# TB_Driver.net
KiCad netlist of a schematic drawn in Altium Designer
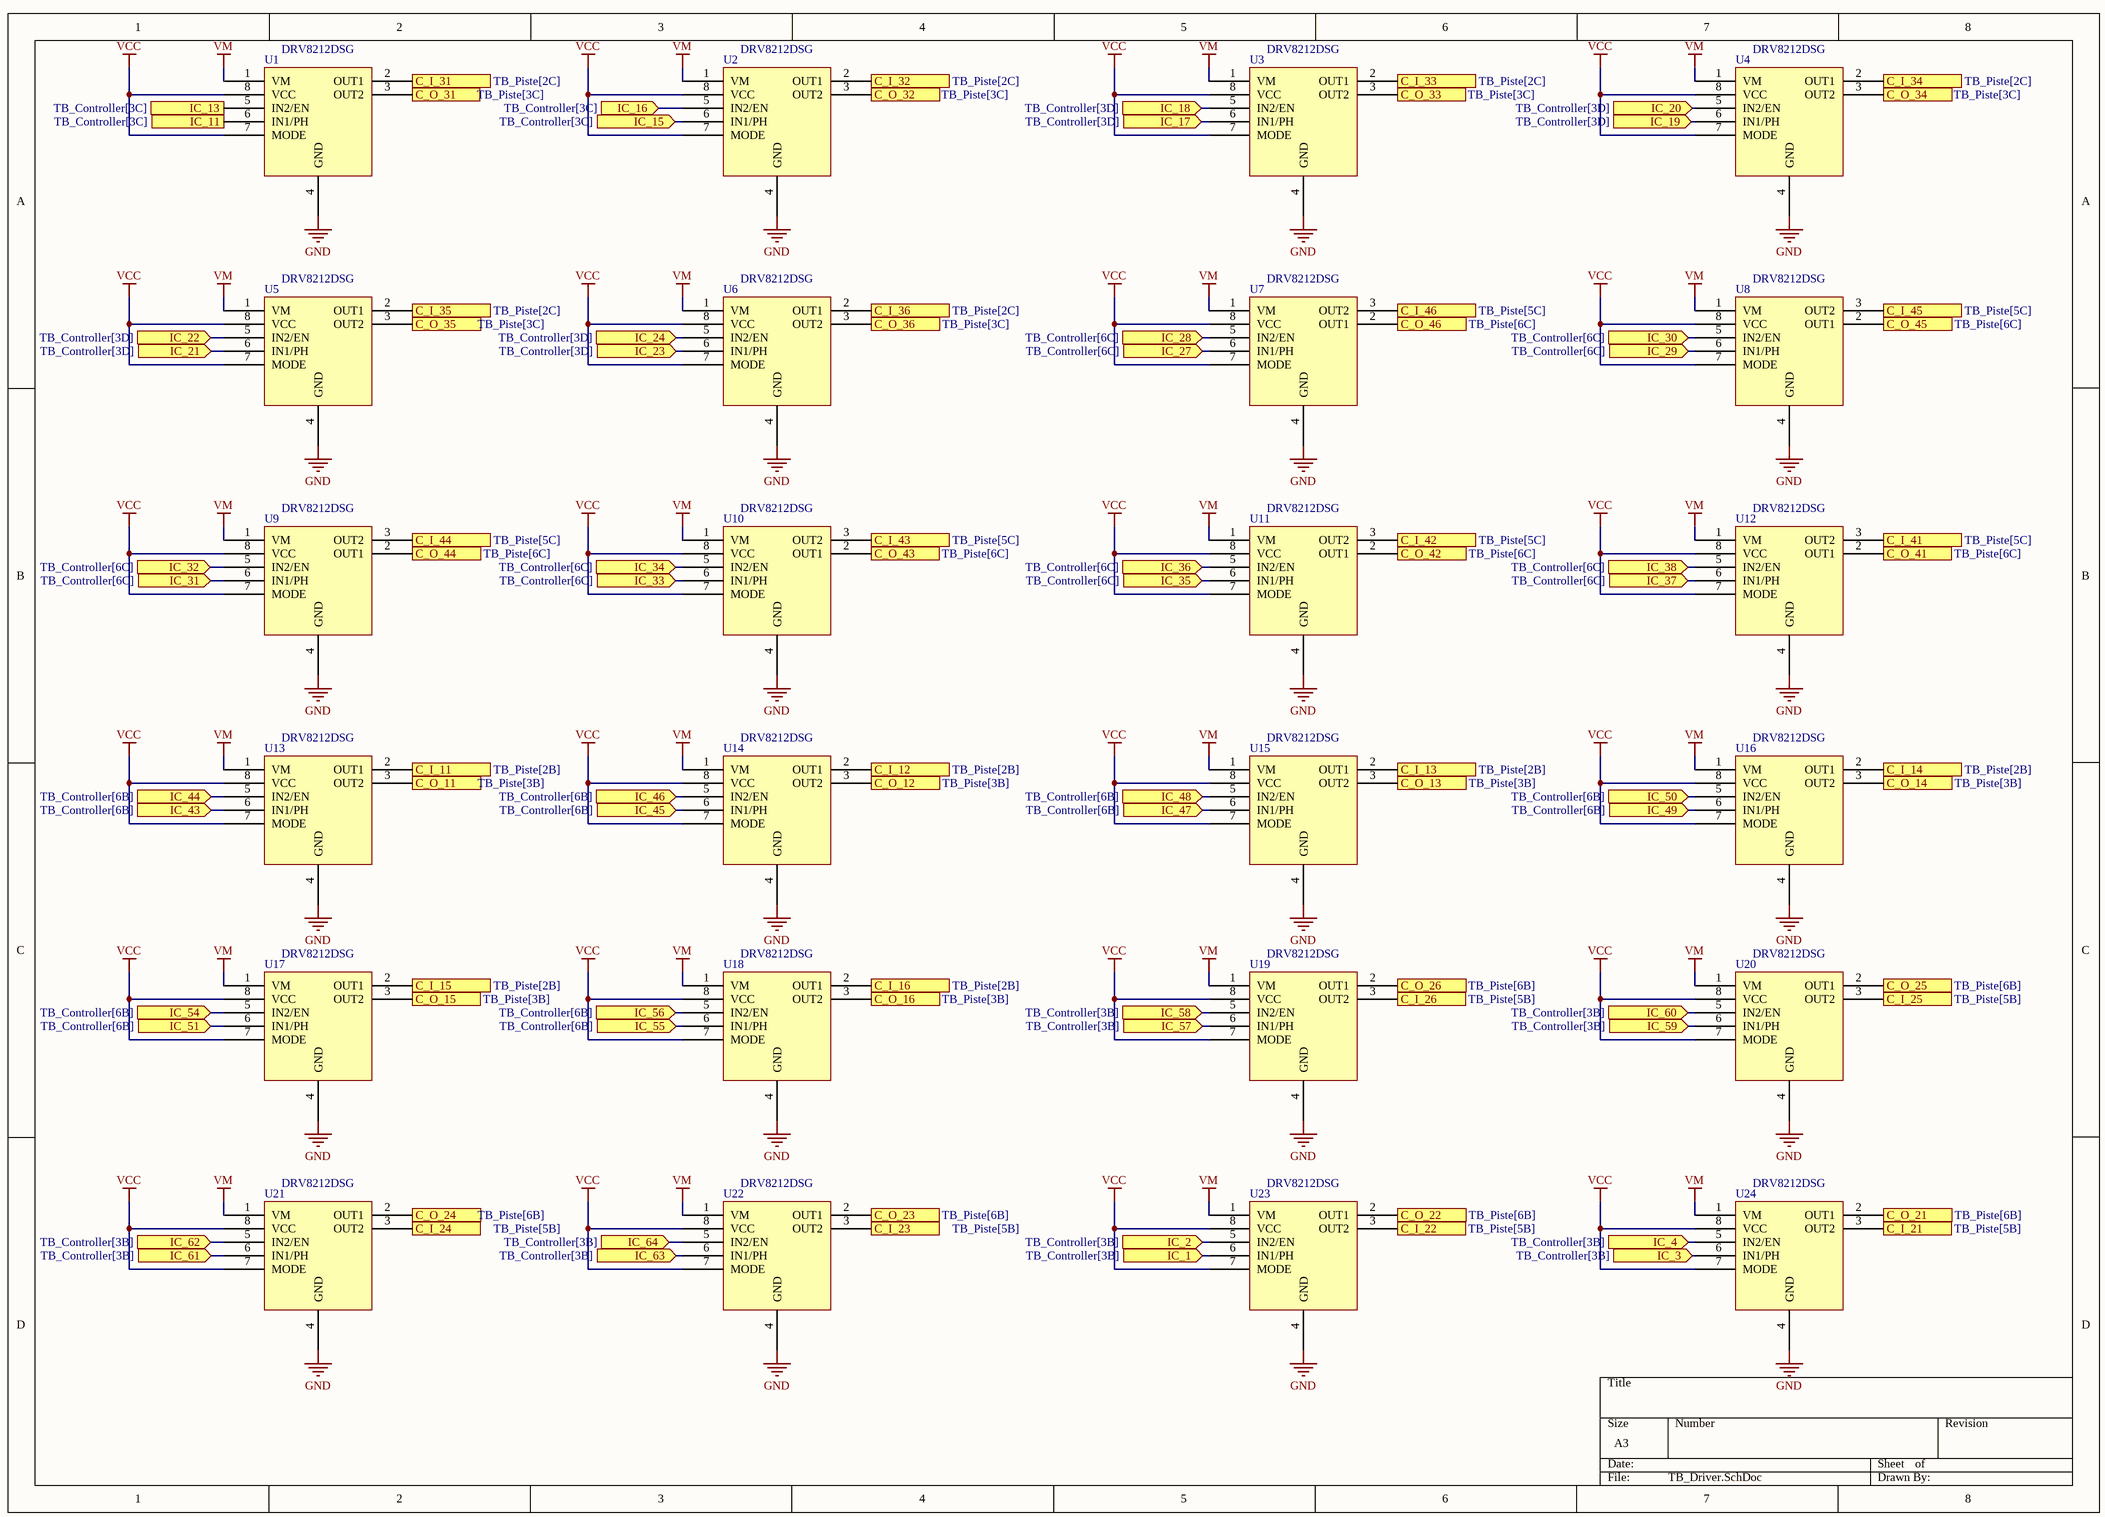
[diagram p0: TB_Driver.SchDoc]

(export (version "E")
  (design (tool "Eeschema 10.0.6"))
  (components
    (comp (ref "U1")
      (value "DRV8212DSG")
      (footprint "DRV8212DSGR")
      (libsource (lib "TB_Components") (part "DRV8212DSG"))
    )
    (comp (ref "U2")
      (value "DRV8212DSG")
      (footprint "DRV8212DSGR")
      (libsource (lib "TB_Components") (part "DRV8212DSG"))
    )
    (comp (ref "U3")
      (value "DRV8212DSG")
      (footprint "DRV8212DSGR")
      (libsource (lib "TB_Components") (part "DRV8212DSG"))
    )
    (comp (ref "U4")
      (value "DRV8212DSG")
      (footprint "DRV8212DSGR")
      (libsource (lib "TB_Components") (part "DRV8212DSG"))
    )
    (comp (ref "U5")
      (value "DRV8212DSG")
      (footprint "DRV8212DSGR")
      (libsource (lib "TB_Components") (part "DRV8212DSG"))
    )
    (comp (ref "U6")
      (value "DRV8212DSG")
      (footprint "DRV8212DSGR")
      (libsource (lib "TB_Components") (part "DRV8212DSG"))
    )
    (comp (ref "U7")
      (value "DRV8212DSG")
      (footprint "DRV8212DSGR")
      (libsource (lib "") (part "DRV8212DSG_1"))
    )
    (comp (ref "U8")
      (value "DRV8212DSG")
      (footprint "DRV8212DSGR")
      (libsource (lib "") (part "DRV8212DSG_1"))
    )
    (comp (ref "U9")
      (value "DRV8212DSG")
      (footprint "DRV8212DSGR")
      (libsource (lib "") (part "DRV8212DSG_1"))
    )
    (comp (ref "U10")
      (value "DRV8212DSG")
      (footprint "DRV8212DSGR")
      (libsource (lib "") (part "DRV8212DSG_1"))
    )
    (comp (ref "U11")
      (value "DRV8212DSG")
      (footprint "DRV8212DSGR")
      (libsource (lib "") (part "DRV8212DSG_1"))
    )
    (comp (ref "U12")
      (value "DRV8212DSG")
      (footprint "DRV8212DSGR")
      (libsource (lib "") (part "DRV8212DSG_1"))
    )
    (comp (ref "U13")
      (value "DRV8212DSG")
      (footprint "DRV8212DSGR")
      (libsource (lib "TB_Components") (part "DRV8212DSG"))
    )
    (comp (ref "U14")
      (value "DRV8212DSG")
      (footprint "DRV8212DSGR")
      (libsource (lib "TB_Components") (part "DRV8212DSG"))
    )
    (comp (ref "U15")
      (value "DRV8212DSG")
      (footprint "DRV8212DSGR")
      (libsource (lib "TB_Components") (part "DRV8212DSG"))
    )
    (comp (ref "U16")
      (value "DRV8212DSG")
      (footprint "DRV8212DSGR")
      (libsource (lib "TB_Components") (part "DRV8212DSG"))
    )
    (comp (ref "U17")
      (value "DRV8212DSG")
      (footprint "DRV8212DSGR")
      (libsource (lib "TB_Components") (part "DRV8212DSG"))
    )
    (comp (ref "U18")
      (value "DRV8212DSG")
      (footprint "DRV8212DSGR")
      (libsource (lib "TB_Components") (part "DRV8212DSG"))
    )
    (comp (ref "U19")
      (value "DRV8212DSG")
      (footprint "DRV8212DSGR")
      (libsource (lib "TB_Components") (part "DRV8212DSG"))
    )
    (comp (ref "U20")
      (value "DRV8212DSG")
      (footprint "DRV8212DSGR")
      (libsource (lib "TB_Components") (part "DRV8212DSG"))
    )
    (comp (ref "U21")
      (value "DRV8212DSG")
      (footprint "DRV8212DSGR")
      (libsource (lib "TB_Components") (part "DRV8212DSG"))
    )
    (comp (ref "U22")
      (value "DRV8212DSG")
      (footprint "DRV8212DSGR")
      (libsource (lib "TB_Components") (part "DRV8212DSG"))
    )
    (comp (ref "U23")
      (value "DRV8212DSG")
      (footprint "DRV8212DSGR")
      (libsource (lib "TB_Components") (part "DRV8212DSG"))
    )
    (comp (ref "U24")
      (value "DRV8212DSG")
      (footprint "DRV8212DSGR")
      (libsource (lib "TB_Components") (part "DRV8212DSG"))
    )
  )
  (nets
    (net (code "1") (name "/C_I_11") (class "Default")
      (node (ref "U13") (pin "2") (pinfunction "OUT1_2") (pintype "passive"))
    )
    (net (code "2") (name "/C_I_12") (class "Default")
      (node (ref "U14") (pin "2") (pinfunction "OUT1_2") (pintype "passive"))
    )
    (net (code "3") (name "/C_I_13") (class "Default")
      (node (ref "U15") (pin "2") (pinfunction "OUT1_2") (pintype "passive"))
    )
    (net (code "4") (name "/C_I_14") (class "Default")
      (node (ref "U16") (pin "2") (pinfunction "OUT1_2") (pintype "passive"))
    )
    (net (code "5") (name "/C_I_15") (class "Default")
      (node (ref "U17") (pin "2") (pinfunction "OUT1_2") (pintype "passive"))
    )
    (net (code "6") (name "/C_I_16") (class "Default")
      (node (ref "U18") (pin "2") (pinfunction "OUT1_2") (pintype "passive"))
    )
    (net (code "7") (name "/C_I_21") (class "Default")
      (node (ref "U24") (pin "3") (pinfunction "OUT2_3") (pintype "passive"))
    )
    (net (code "8") (name "/C_I_22") (class "Default")
      (node (ref "U23") (pin "3") (pinfunction "OUT2_3") (pintype "passive"))
    )
    (net (code "9") (name "/C_I_23") (class "Default")
      (node (ref "U22") (pin "3") (pinfunction "OUT2_3") (pintype "passive"))
    )
    (net (code "10") (name "/C_I_24") (class "Default")
      (node (ref "U21") (pin "3") (pinfunction "OUT2_3") (pintype "passive"))
    )
    (net (code "11") (name "/C_I_25") (class "Default")
      (node (ref "U20") (pin "3") (pinfunction "OUT2_3") (pintype "passive"))
    )
    (net (code "12") (name "/C_I_26") (class "Default")
      (node (ref "U19") (pin "3") (pinfunction "OUT2_3") (pintype "passive"))
    )
    (net (code "13") (name "/C_I_31") (class "Default")
      (node (ref "U1") (pin "2") (pinfunction "OUT1_2") (pintype "passive"))
    )
    (net (code "14") (name "/C_I_32") (class "Default")
      (node (ref "U2") (pin "2") (pinfunction "OUT1_2") (pintype "passive"))
    )
    (net (code "15") (name "/C_I_33") (class "Default")
      (node (ref "U3") (pin "2") (pinfunction "OUT1_2") (pintype "passive"))
    )
    (net (code "16") (name "/C_I_34") (class "Default")
      (node (ref "U4") (pin "2") (pinfunction "OUT1_2") (pintype "passive"))
    )
    (net (code "17") (name "/C_I_35") (class "Default")
      (node (ref "U5") (pin "2") (pinfunction "OUT1_2") (pintype "passive"))
    )
    (net (code "18") (name "/C_I_36") (class "Default")
      (node (ref "U6") (pin "2") (pinfunction "OUT1_2") (pintype "passive"))
    )
    (net (code "19") (name "/C_I_41") (class "Default")
      (node (ref "U12") (pin "3") (pinfunction "OUT2_3") (pintype "passive"))
    )
    (net (code "20") (name "/C_I_42") (class "Default")
      (node (ref "U11") (pin "3") (pinfunction "OUT2_3") (pintype "passive"))
    )
    (net (code "21") (name "/C_I_43") (class "Default")
      (node (ref "U10") (pin "3") (pinfunction "OUT2_3") (pintype "passive"))
    )
    (net (code "22") (name "/C_I_44") (class "Default")
      (node (ref "U9") (pin "3") (pinfunction "OUT2_3") (pintype "passive"))
    )
    (net (code "23") (name "/C_I_45") (class "Default")
      (node (ref "U8") (pin "3") (pinfunction "OUT2_3") (pintype "passive"))
    )
    (net (code "24") (name "/C_I_46") (class "Default")
      (node (ref "U7") (pin "3") (pinfunction "OUT2_3") (pintype "passive"))
    )
    (net (code "25") (name "/C_O_11") (class "Default")
      (node (ref "U13") (pin "3") (pinfunction "OUT2_3") (pintype "passive"))
    )
    (net (code "26") (name "/C_O_12") (class "Default")
      (node (ref "U14") (pin "3") (pinfunction "OUT2_3") (pintype "passive"))
    )
    (net (code "27") (name "/C_O_13") (class "Default")
      (node (ref "U15") (pin "3") (pinfunction "OUT2_3") (pintype "passive"))
    )
    (net (code "28") (name "/C_O_14") (class "Default")
      (node (ref "U16") (pin "3") (pinfunction "OUT2_3") (pintype "passive"))
    )
    (net (code "29") (name "/C_O_15") (class "Default")
      (node (ref "U17") (pin "3") (pinfunction "OUT2_3") (pintype "passive"))
    )
    (net (code "30") (name "/C_O_16") (class "Default")
      (node (ref "U18") (pin "3") (pinfunction "OUT2_3") (pintype "passive"))
    )
    (net (code "31") (name "/C_O_21") (class "Default")
      (node (ref "U24") (pin "2") (pinfunction "OUT1_2") (pintype "passive"))
    )
    (net (code "32") (name "/C_O_22") (class "Default")
      (node (ref "U23") (pin "2") (pinfunction "OUT1_2") (pintype "passive"))
    )
    (net (code "33") (name "/C_O_23") (class "Default")
      (node (ref "U22") (pin "2") (pinfunction "OUT1_2") (pintype "passive"))
    )
    (net (code "34") (name "/C_O_24") (class "Default")
      (node (ref "U21") (pin "2") (pinfunction "OUT1_2") (pintype "passive"))
    )
    (net (code "35") (name "/C_O_25") (class "Default")
      (node (ref "U20") (pin "2") (pinfunction "OUT1_2") (pintype "passive"))
    )
    (net (code "36") (name "/C_O_26") (class "Default")
      (node (ref "U19") (pin "2") (pinfunction "OUT1_2") (pintype "passive"))
    )
    (net (code "37") (name "/C_O_31") (class "Default")
      (node (ref "U1") (pin "3") (pinfunction "OUT2_3") (pintype "passive"))
    )
    (net (code "38") (name "/C_O_32") (class "Default")
      (node (ref "U2") (pin "3") (pinfunction "OUT2_3") (pintype "passive"))
    )
    (net (code "39") (name "/C_O_33") (class "Default")
      (node (ref "U3") (pin "3") (pinfunction "OUT2_3") (pintype "passive"))
    )
    (net (code "40") (name "/C_O_34") (class "Default")
      (node (ref "U4") (pin "3") (pinfunction "OUT2_3") (pintype "passive"))
    )
    (net (code "41") (name "/C_O_35") (class "Default")
      (node (ref "U5") (pin "3") (pinfunction "OUT2_3") (pintype "passive"))
    )
    (net (code "42") (name "/C_O_36") (class "Default")
      (node (ref "U6") (pin "3") (pinfunction "OUT2_3") (pintype "passive"))
    )
    (net (code "43") (name "/C_O_41") (class "Default")
      (node (ref "U12") (pin "2") (pinfunction "OUT1_2") (pintype "passive"))
    )
    (net (code "44") (name "/C_O_42") (class "Default")
      (node (ref "U11") (pin "2") (pinfunction "OUT1_2") (pintype "passive"))
    )
    (net (code "45") (name "/C_O_43") (class "Default")
      (node (ref "U10") (pin "2") (pinfunction "OUT1_2") (pintype "passive"))
    )
    (net (code "46") (name "/C_O_44") (class "Default")
      (node (ref "U9") (pin "2") (pinfunction "OUT1_2") (pintype "passive"))
    )
    (net (code "47") (name "/C_O_45") (class "Default")
      (node (ref "U8") (pin "2") (pinfunction "OUT1_2") (pintype "passive"))
    )
    (net (code "48") (name "/C_O_46") (class "Default")
      (node (ref "U7") (pin "2") (pinfunction "OUT1_2") (pintype "passive"))
    )
    (net (code "49") (name "/IC_1") (class "Default")
      (node (ref "U23") (pin "6") (pinfunction "IN1/PH_6") (pintype "passive"))
    )
    (net (code "50") (name "/IC_2") (class "Default")
      (node (ref "U23") (pin "5") (pinfunction "IN2/EN_5") (pintype "passive"))
    )
    (net (code "51") (name "/IC_3") (class "Default")
      (node (ref "U24") (pin "6") (pinfunction "IN1/PH_6") (pintype "passive"))
    )
    (net (code "52") (name "/IC_4") (class "Default")
      (node (ref "U24") (pin "5") (pinfunction "IN2/EN_5") (pintype "passive"))
    )
    (net (code "53") (name "/IC_11") (class "Default")
      (node (ref "U1") (pin "6") (pinfunction "IN1/PH_6") (pintype "passive"))
    )
    (net (code "54") (name "/IC_13") (class "Default")
      (node (ref "U1") (pin "5") (pinfunction "IN2/EN_5") (pintype "passive"))
    )
    (net (code "55") (name "/IC_15") (class "Default")
      (node (ref "U2") (pin "6") (pinfunction "IN1/PH_6") (pintype "passive"))
    )
    (net (code "56") (name "/IC_16") (class "Default")
      (node (ref "U2") (pin "5") (pinfunction "IN2/EN_5") (pintype "passive"))
    )
    (net (code "57") (name "/IC_17") (class "Default")
      (node (ref "U3") (pin "6") (pinfunction "IN1/PH_6") (pintype "passive"))
    )
    (net (code "58") (name "/IC_18") (class "Default")
      (node (ref "U3") (pin "5") (pinfunction "IN2/EN_5") (pintype "passive"))
    )
    (net (code "59") (name "/IC_19") (class "Default")
      (node (ref "U4") (pin "6") (pinfunction "IN1/PH_6") (pintype "passive"))
    )
    (net (code "60") (name "/IC_20") (class "Default")
      (node (ref "U4") (pin "5") (pinfunction "IN2/EN_5") (pintype "passive"))
    )
    (net (code "61") (name "/IC_21") (class "Default")
      (node (ref "U5") (pin "6") (pinfunction "IN1/PH_6") (pintype "passive"))
    )
    (net (code "62") (name "/IC_22") (class "Default")
      (node (ref "U5") (pin "5") (pinfunction "IN2/EN_5") (pintype "passive"))
    )
    (net (code "63") (name "/IC_23") (class "Default")
      (node (ref "U6") (pin "6") (pinfunction "IN1/PH_6") (pintype "passive"))
    )
    (net (code "64") (name "/IC_24") (class "Default")
      (node (ref "U6") (pin "5") (pinfunction "IN2/EN_5") (pintype "passive"))
    )
    (net (code "65") (name "/IC_27") (class "Default")
      (node (ref "U7") (pin "6") (pinfunction "IN1/PH_6") (pintype "passive"))
    )
    (net (code "66") (name "/IC_28") (class "Default")
      (node (ref "U7") (pin "5") (pinfunction "IN2/EN_5") (pintype "passive"))
    )
    (net (code "67") (name "/IC_29") (class "Default")
      (node (ref "U8") (pin "6") (pinfunction "IN1/PH_6") (pintype "passive"))
    )
    (net (code "68") (name "/IC_30") (class "Default")
      (node (ref "U8") (pin "5") (pinfunction "IN2/EN_5") (pintype "passive"))
    )
    (net (code "69") (name "/IC_31") (class "Default")
      (node (ref "U9") (pin "6") (pinfunction "IN1/PH_6") (pintype "passive"))
    )
    (net (code "70") (name "/IC_32") (class "Default")
      (node (ref "U9") (pin "5") (pinfunction "IN2/EN_5") (pintype "passive"))
    )
    (net (code "71") (name "/IC_33") (class "Default")
      (node (ref "U10") (pin "6") (pinfunction "IN1/PH_6") (pintype "passive"))
    )
    (net (code "72") (name "/IC_34") (class "Default")
      (node (ref "U10") (pin "5") (pinfunction "IN2/EN_5") (pintype "passive"))
    )
    (net (code "73") (name "/IC_35") (class "Default")
      (node (ref "U11") (pin "6") (pinfunction "IN1/PH_6") (pintype "passive"))
    )
    (net (code "74") (name "/IC_36") (class "Default")
      (node (ref "U11") (pin "5") (pinfunction "IN2/EN_5") (pintype "passive"))
    )
    (net (code "75") (name "/IC_37") (class "Default")
      (node (ref "U12") (pin "6") (pinfunction "IN1/PH_6") (pintype "passive"))
    )
    (net (code "76") (name "/IC_38") (class "Default")
      (node (ref "U12") (pin "5") (pinfunction "IN2/EN_5") (pintype "passive"))
    )
    (net (code "77") (name "/IC_43") (class "Default")
      (node (ref "U13") (pin "6") (pinfunction "IN1/PH_6") (pintype "passive"))
    )
    (net (code "78") (name "/IC_44") (class "Default")
      (node (ref "U13") (pin "5") (pinfunction "IN2/EN_5") (pintype "passive"))
    )
    (net (code "79") (name "/IC_45") (class "Default")
      (node (ref "U14") (pin "6") (pinfunction "IN1/PH_6") (pintype "passive"))
    )
    (net (code "80") (name "/IC_46") (class "Default")
      (node (ref "U14") (pin "5") (pinfunction "IN2/EN_5") (pintype "passive"))
    )
    (net (code "81") (name "/IC_47") (class "Default")
      (node (ref "U15") (pin "6") (pinfunction "IN1/PH_6") (pintype "passive"))
    )
    (net (code "82") (name "/IC_48") (class "Default")
      (node (ref "U15") (pin "5") (pinfunction "IN2/EN_5") (pintype "passive"))
    )
    (net (code "83") (name "/IC_49") (class "Default")
      (node (ref "U16") (pin "6") (pinfunction "IN1/PH_6") (pintype "passive"))
    )
    (net (code "84") (name "/IC_50") (class "Default")
      (node (ref "U16") (pin "5") (pinfunction "IN2/EN_5") (pintype "passive"))
    )
    (net (code "85") (name "/IC_51") (class "Default")
      (node (ref "U17") (pin "6") (pinfunction "IN1/PH_6") (pintype "passive"))
    )
    (net (code "86") (name "/IC_54") (class "Default")
      (node (ref "U17") (pin "5") (pinfunction "IN2/EN_5") (pintype "passive"))
    )
    (net (code "87") (name "/IC_55") (class "Default")
      (node (ref "U18") (pin "6") (pinfunction "IN1/PH_6") (pintype "passive"))
    )
    (net (code "88") (name "/IC_56") (class "Default")
      (node (ref "U18") (pin "5") (pinfunction "IN2/EN_5") (pintype "passive"))
    )
    (net (code "89") (name "/IC_57") (class "Default")
      (node (ref "U19") (pin "6") (pinfunction "IN1/PH_6") (pintype "passive"))
    )
    (net (code "90") (name "/IC_58") (class "Default")
      (node (ref "U19") (pin "5") (pinfunction "IN2/EN_5") (pintype "passive"))
    )
    (net (code "91") (name "/IC_59") (class "Default")
      (node (ref "U20") (pin "6") (pinfunction "IN1/PH_6") (pintype "passive"))
    )
    (net (code "92") (name "/IC_60") (class "Default")
      (node (ref "U20") (pin "5") (pinfunction "IN2/EN_5") (pintype "passive"))
    )
    (net (code "93") (name "/IC_61") (class "Default")
      (node (ref "U21") (pin "6") (pinfunction "IN1/PH_6") (pintype "passive"))
    )
    (net (code "94") (name "/IC_62") (class "Default")
      (node (ref "U21") (pin "5") (pinfunction "IN2/EN_5") (pintype "passive"))
    )
    (net (code "95") (name "/IC_63") (class "Default")
      (node (ref "U22") (pin "6") (pinfunction "IN1/PH_6") (pintype "passive"))
    )
    (net (code "96") (name "/IC_64") (class "Default")
      (node (ref "U22") (pin "5") (pinfunction "IN2/EN_5") (pintype "passive"))
    )
    (net (code "97") (name "GND") (class "Default")
      (node (ref "U1") (pin "4") (pinfunction "GND_4") (pintype "passive"))
      (node (ref "U10") (pin "4") (pinfunction "GND_4") (pintype "passive"))
      (node (ref "U11") (pin "4") (pinfunction "GND_4") (pintype "passive"))
      (node (ref "U12") (pin "4") (pinfunction "GND_4") (pintype "passive"))
      (node (ref "U13") (pin "4") (pinfunction "GND_4") (pintype "passive"))
      (node (ref "U14") (pin "4") (pinfunction "GND_4") (pintype "passive"))
      (node (ref "U15") (pin "4") (pinfunction "GND_4") (pintype "passive"))
      (node (ref "U16") (pin "4") (pinfunction "GND_4") (pintype "passive"))
      (node (ref "U17") (pin "4") (pinfunction "GND_4") (pintype "passive"))
      (node (ref "U18") (pin "4") (pinfunction "GND_4") (pintype "passive"))
      (node (ref "U19") (pin "4") (pinfunction "GND_4") (pintype "passive"))
      (node (ref "U2") (pin "4") (pinfunction "GND_4") (pintype "passive"))
      (node (ref "U20") (pin "4") (pinfunction "GND_4") (pintype "passive"))
      (node (ref "U21") (pin "4") (pinfunction "GND_4") (pintype "passive"))
      (node (ref "U22") (pin "4") (pinfunction "GND_4") (pintype "passive"))
      (node (ref "U23") (pin "4") (pinfunction "GND_4") (pintype "passive"))
      (node (ref "U24") (pin "4") (pinfunction "GND_4") (pintype "passive"))
      (node (ref "U3") (pin "4") (pinfunction "GND_4") (pintype "passive"))
      (node (ref "U4") (pin "4") (pinfunction "GND_4") (pintype "passive"))
      (node (ref "U5") (pin "4") (pinfunction "GND_4") (pintype "passive"))
      (node (ref "U6") (pin "4") (pinfunction "GND_4") (pintype "passive"))
      (node (ref "U7") (pin "4") (pinfunction "GND_4") (pintype "passive"))
      (node (ref "U8") (pin "4") (pinfunction "GND_4") (pintype "passive"))
      (node (ref "U9") (pin "4") (pinfunction "GND_4") (pintype "passive"))
    )
    (net (code "98") (name "VCC") (class "Default")
      (node (ref "U1") (pin "7") (pinfunction "MODE_7") (pintype "passive"))
      (node (ref "U1") (pin "8") (pinfunction "VCC_8") (pintype "passive"))
      (node (ref "U10") (pin "7") (pinfunction "MODE_7") (pintype "passive"))
      (node (ref "U10") (pin "8") (pinfunction "VCC_8") (pintype "passive"))
      (node (ref "U11") (pin "7") (pinfunction "MODE_7") (pintype "passive"))
      (node (ref "U11") (pin "8") (pinfunction "VCC_8") (pintype "passive"))
      (node (ref "U12") (pin "7") (pinfunction "MODE_7") (pintype "passive"))
      (node (ref "U12") (pin "8") (pinfunction "VCC_8") (pintype "passive"))
      (node (ref "U13") (pin "7") (pinfunction "MODE_7") (pintype "passive"))
      (node (ref "U13") (pin "8") (pinfunction "VCC_8") (pintype "passive"))
      (node (ref "U14") (pin "7") (pinfunction "MODE_7") (pintype "passive"))
      (node (ref "U14") (pin "8") (pinfunction "VCC_8") (pintype "passive"))
      (node (ref "U15") (pin "7") (pinfunction "MODE_7") (pintype "passive"))
      (node (ref "U15") (pin "8") (pinfunction "VCC_8") (pintype "passive"))
      (node (ref "U16") (pin "7") (pinfunction "MODE_7") (pintype "passive"))
      (node (ref "U16") (pin "8") (pinfunction "VCC_8") (pintype "passive"))
      (node (ref "U17") (pin "7") (pinfunction "MODE_7") (pintype "passive"))
      (node (ref "U17") (pin "8") (pinfunction "VCC_8") (pintype "passive"))
      (node (ref "U18") (pin "7") (pinfunction "MODE_7") (pintype "passive"))
      (node (ref "U18") (pin "8") (pinfunction "VCC_8") (pintype "passive"))
      (node (ref "U19") (pin "7") (pinfunction "MODE_7") (pintype "passive"))
      (node (ref "U19") (pin "8") (pinfunction "VCC_8") (pintype "passive"))
      (node (ref "U2") (pin "7") (pinfunction "MODE_7") (pintype "passive"))
      (node (ref "U2") (pin "8") (pinfunction "VCC_8") (pintype "passive"))
      (node (ref "U20") (pin "7") (pinfunction "MODE_7") (pintype "passive"))
      (node (ref "U20") (pin "8") (pinfunction "VCC_8") (pintype "passive"))
      (node (ref "U21") (pin "7") (pinfunction "MODE_7") (pintype "passive"))
      (node (ref "U21") (pin "8") (pinfunction "VCC_8") (pintype "passive"))
      (node (ref "U22") (pin "7") (pinfunction "MODE_7") (pintype "passive"))
      (node (ref "U22") (pin "8") (pinfunction "VCC_8") (pintype "passive"))
      (node (ref "U23") (pin "7") (pinfunction "MODE_7") (pintype "passive"))
      (node (ref "U23") (pin "8") (pinfunction "VCC_8") (pintype "passive"))
      (node (ref "U24") (pin "7") (pinfunction "MODE_7") (pintype "passive"))
      (node (ref "U24") (pin "8") (pinfunction "VCC_8") (pintype "passive"))
      (node (ref "U3") (pin "7") (pinfunction "MODE_7") (pintype "passive"))
      (node (ref "U3") (pin "8") (pinfunction "VCC_8") (pintype "passive"))
      (node (ref "U4") (pin "7") (pinfunction "MODE_7") (pintype "passive"))
      (node (ref "U4") (pin "8") (pinfunction "VCC_8") (pintype "passive"))
      (node (ref "U5") (pin "7") (pinfunction "MODE_7") (pintype "passive"))
      (node (ref "U5") (pin "8") (pinfunction "VCC_8") (pintype "passive"))
      (node (ref "U6") (pin "7") (pinfunction "MODE_7") (pintype "passive"))
      (node (ref "U6") (pin "8") (pinfunction "VCC_8") (pintype "passive"))
      (node (ref "U7") (pin "7") (pinfunction "MODE_7") (pintype "passive"))
      (node (ref "U7") (pin "8") (pinfunction "VCC_8") (pintype "passive"))
      (node (ref "U8") (pin "7") (pinfunction "MODE_7") (pintype "passive"))
      (node (ref "U8") (pin "8") (pinfunction "VCC_8") (pintype "passive"))
      (node (ref "U9") (pin "7") (pinfunction "MODE_7") (pintype "passive"))
      (node (ref "U9") (pin "8") (pinfunction "VCC_8") (pintype "passive"))
    )
    (net (code "99") (name "VM") (class "Default")
      (node (ref "U1") (pin "1") (pinfunction "VM_1") (pintype "passive"))
      (node (ref "U10") (pin "1") (pinfunction "VM_1") (pintype "passive"))
      (node (ref "U11") (pin "1") (pinfunction "VM_1") (pintype "passive"))
      (node (ref "U12") (pin "1") (pinfunction "VM_1") (pintype "passive"))
      (node (ref "U13") (pin "1") (pinfunction "VM_1") (pintype "passive"))
      (node (ref "U14") (pin "1") (pinfunction "VM_1") (pintype "passive"))
      (node (ref "U15") (pin "1") (pinfunction "VM_1") (pintype "passive"))
      (node (ref "U16") (pin "1") (pinfunction "VM_1") (pintype "passive"))
      (node (ref "U17") (pin "1") (pinfunction "VM_1") (pintype "passive"))
      (node (ref "U18") (pin "1") (pinfunction "VM_1") (pintype "passive"))
      (node (ref "U19") (pin "1") (pinfunction "VM_1") (pintype "passive"))
      (node (ref "U2") (pin "1") (pinfunction "VM_1") (pintype "passive"))
      (node (ref "U20") (pin "1") (pinfunction "VM_1") (pintype "passive"))
      (node (ref "U21") (pin "1") (pinfunction "VM_1") (pintype "passive"))
      (node (ref "U22") (pin "1") (pinfunction "VM_1") (pintype "passive"))
      (node (ref "U23") (pin "1") (pinfunction "VM_1") (pintype "passive"))
      (node (ref "U24") (pin "1") (pinfunction "VM_1") (pintype "passive"))
      (node (ref "U3") (pin "1") (pinfunction "VM_1") (pintype "passive"))
      (node (ref "U4") (pin "1") (pinfunction "VM_1") (pintype "passive"))
      (node (ref "U5") (pin "1") (pinfunction "VM_1") (pintype "passive"))
      (node (ref "U6") (pin "1") (pinfunction "VM_1") (pintype "passive"))
      (node (ref "U7") (pin "1") (pinfunction "VM_1") (pintype "passive"))
      (node (ref "U8") (pin "1") (pinfunction "VM_1") (pintype "passive"))
      (node (ref "U9") (pin "1") (pinfunction "VM_1") (pintype "passive"))
    )
  )
)
